# subckt_6V0_SMPS.net
KiCad netlist of a schematic drawn in Altium Designer
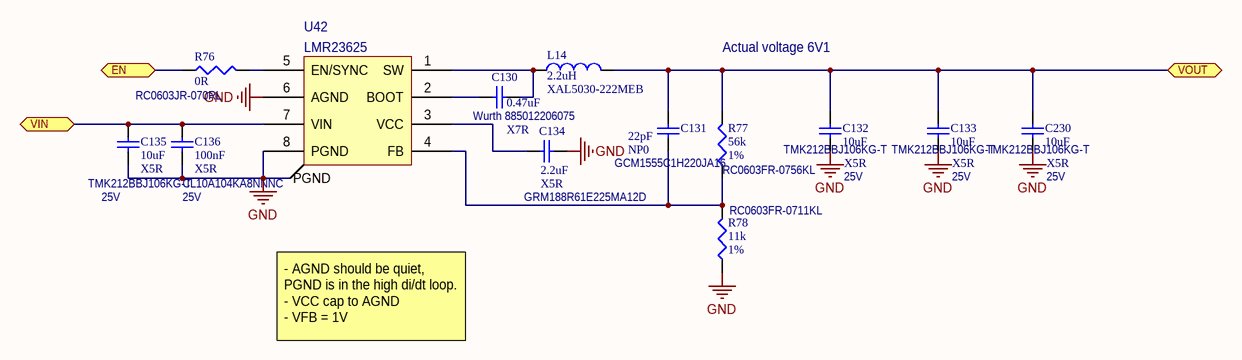
[diagram p0: subckt_6V0_SMPS.SchDoc]

(export (version "E")
  (design (tool "Eeschema 10.0.6"))
  (components
    (comp (ref "C130")
      (value "0.47uF")
      (footprint "CAP0603")
      (description "Capacitor")
      (fields (field (name "DIELECTRIC") "X7R") (field (name "MODEL") "Wurth 885012206075"))
      (libsource (lib "lib_basic") (part "Capacitor"))
    )
    (comp (ref "C131")
      (value "22pF")
      (footprint "CAP0402")
      (description "Capacitor")
      (fields (field (name "DIELECTRIC") "NP0") (field (name "MODEL") "GCM1555C1H220JA16"))
      (libsource (lib "lib_basic") (part "Capacitor"))
    )
    (comp (ref "C132")
      (value "10uF")
      (footprint "lib_basic:CAP0805")
      (description "Capacitor")
      (fields
        (field (name "DIELECTRIC") "X5R")
        (field (name "MODEL") "TMK212BBJ106KG-T")
        (field (name "VOLTAGE") "25V")
      )
      (libsource (lib "lib_basic") (part "Capacitor"))
    )
    (comp (ref "C133")
      (value "10uF")
      (footprint "lib_basic:CAP0805")
      (description "Capacitor")
      (fields
        (field (name "DIELECTRIC") "X5R")
        (field (name "MODEL") "TMK212BBJ106KG-T")
        (field (name "VOLTAGE") "25V")
      )
      (libsource (lib "lib_basic") (part "Capacitor"))
    )
    (comp (ref "C134")
      (value "2.2uF")
      (footprint "CAP0603")
      (description "Capacitor")
      (fields (field (name "DIELECTRIC") "X5R") (field (name "MODEL") "GRM188R61E225MA12D"))
      (libsource (lib "lib_basic") (part "Capacitor"))
    )
    (comp (ref "C135")
      (value "10uF")
      (footprint "lib_basic:CAP0805")
      (description "Capacitor")
      (fields
        (field (name "DIELECTRIC") "X5R")
        (field (name "MODEL") "TMK212BBJ106KG-T")
        (field (name "VOLTAGE") "25V")
      )
      (libsource (lib "lib_basic") (part "Capacitor"))
    )
    (comp (ref "C136")
      (value "100nF")
      (footprint "CAP0603")
      (description "Capacitor")
      (fields
        (field (name "DIELECTRIC") "X5R")
        (field (name "MODEL") "CL10A104KA8NNNC")
        (field (name "VOLTAGE") "25V")
      )
      (libsource (lib "lib_basic") (part "Capacitor"))
    )
    (comp (ref "C230")
      (value "10uF")
      (footprint "lib_basic:CAP0805")
      (description "Capacitor")
      (fields
        (field (name "DIELECTRIC") "X5R")
        (field (name "MODEL") "TMK212BBJ106KG-T")
        (field (name "VOLTAGE") "25V")
      )
      (libsource (lib "lib_basic") (part "Capacitor"))
    )
    (comp (ref "L14")
      (value "2.2uH")
      (footprint "lib_basic:IND XAL50")
      (description "Inductor")
      (fields (field (name "MODEL") "XAL5030-222MEB") (field (name "Comment") ">2A"))
      (libsource (lib "lib_basic") (part "Inductor"))
    )
    (comp (ref "R76")
      (value "0R")
      (footprint "RES0603")
      (description "Resistor")
      (fields (field (name "MODEL") "RC0603JR-070RL"))
      (libsource (lib "lib_basic") (part "Resistor"))
    )
    (comp (ref "R77")
      (value "56k")
      (footprint "RES0603")
      (description "Resistor")
      (fields (field (name "TYPE") "1%") (field (name "MODEL") "RC0603FR-0756KL"))
      (libsource (lib "lib_basic") (part "Resistor"))
    )
    (comp (ref "R78")
      (value "11k")
      (footprint "RES0603")
      (description "Resistor")
      (fields (field (name "TYPE") "1%") (field (name "MODEL") "RC0603FR-0711KL"))
      (libsource (lib "lib_basic") (part "Resistor"))
    )
    (comp (ref "U42")
      (value "LMR23625")
      (footprint "lib_basic:SOIC8 Thermal Pad")
      (description "2.5A Simple Switcher sync buck")
      (libsource (lib "lib_TI_Power") (part "LMR23625"))
    )
  )
  (nets
    (net (code "1") (name "/EN") (class "Default")
      (node (ref "R76") (pin "1") (pinfunction "1_1") (pintype "passive"))
    )
    (net (code "2") (name "/VIN") (class "Default")
      (node (ref "C135") (pin "2") (pinfunction "2_2") (pintype "passive"))
      (node (ref "C136") (pin "2") (pinfunction "2_2") (pintype "passive"))
      (node (ref "U42") (pin "7") (pinfunction "VIN_7") (pintype "passive"))
    )
    (net (code "3") (name "/VOUT") (class "Default")
      (node (ref "C131") (pin "1") (pinfunction "1_1") (pintype "passive"))
      (node (ref "C132") (pin "2") (pinfunction "2_2") (pintype "passive"))
      (node (ref "C133") (pin "2") (pinfunction "2_2") (pintype "passive"))
      (node (ref "C230") (pin "2") (pinfunction "2_2") (pintype "passive"))
      (node (ref "L14") (pin "2") (pinfunction "2_2") (pintype "passive"))
      (node (ref "R77") (pin "2") (pinfunction "2_2") (pintype "passive"))
    )
    (net (code "4") (name "GND") (class "Default")
      (node (ref "C132") (pin "1") (pinfunction "1_1") (pintype "passive"))
      (node (ref "C133") (pin "1") (pinfunction "1_1") (pintype "passive"))
      (node (ref "C134") (pin "2") (pinfunction "2_2") (pintype "passive"))
      (node (ref "C135") (pin "1") (pinfunction "1_1") (pintype "passive"))
      (node (ref "C136") (pin "1") (pinfunction "1_1") (pintype "passive"))
      (node (ref "C230") (pin "1") (pinfunction "1_1") (pintype "passive"))
      (node (ref "R78") (pin "1") (pinfunction "1_1") (pintype "passive"))
      (node (ref "U42") (pin "6") (pinfunction "AGND_6") (pintype "passive"))
      (node (ref "U42") (pin "8") (pinfunction "PGND_8") (pintype "passive"))
      (node (ref "U42") (pin "9") (pinfunction "PGND_9") (pintype "passive"))
    )
    (net (code "5") (name "Net-(U42-BOOT)") (class "Default")
      (node (ref "C130") (pin "2") (pinfunction "2_2") (pintype "passive"))
      (node (ref "U42") (pin "2") (pinfunction "BOOT_2") (pintype "passive"))
    )
    (net (code "6") (name "Net-(U42-EN{slash}SYNC)") (class "Default")
      (node (ref "R76") (pin "2") (pinfunction "2_2") (pintype "passive"))
      (node (ref "U42") (pin "5") (pinfunction "EN/SYNC_5") (pintype "passive"))
    )
    (net (code "7") (name "Net-(U42-FB)") (class "Default")
      (node (ref "C131") (pin "2") (pinfunction "2_2") (pintype "passive"))
      (node (ref "R77") (pin "1") (pinfunction "1_1") (pintype "passive"))
      (node (ref "R78") (pin "2") (pinfunction "2_2") (pintype "passive"))
      (node (ref "U42") (pin "4") (pinfunction "FB_4") (pintype "passive"))
    )
    (net (code "8") (name "Net-(U42-SW)") (class "Default")
      (node (ref "C130") (pin "1") (pinfunction "1_1") (pintype "passive"))
      (node (ref "L14") (pin "1") (pinfunction "1_1") (pintype "passive"))
      (node (ref "U42") (pin "1") (pinfunction "SW_1") (pintype "passive"))
    )
    (net (code "9") (name "Net-(U42-VCC)") (class "Default")
      (node (ref "C134") (pin "1") (pinfunction "1_1") (pintype "passive"))
      (node (ref "U42") (pin "3") (pinfunction "VCC_3") (pintype "passive"))
    )
  )
)
